# 506_outin_raspberrypi_zero.net
KiCad netlist of a schematic drawn in EAGLE
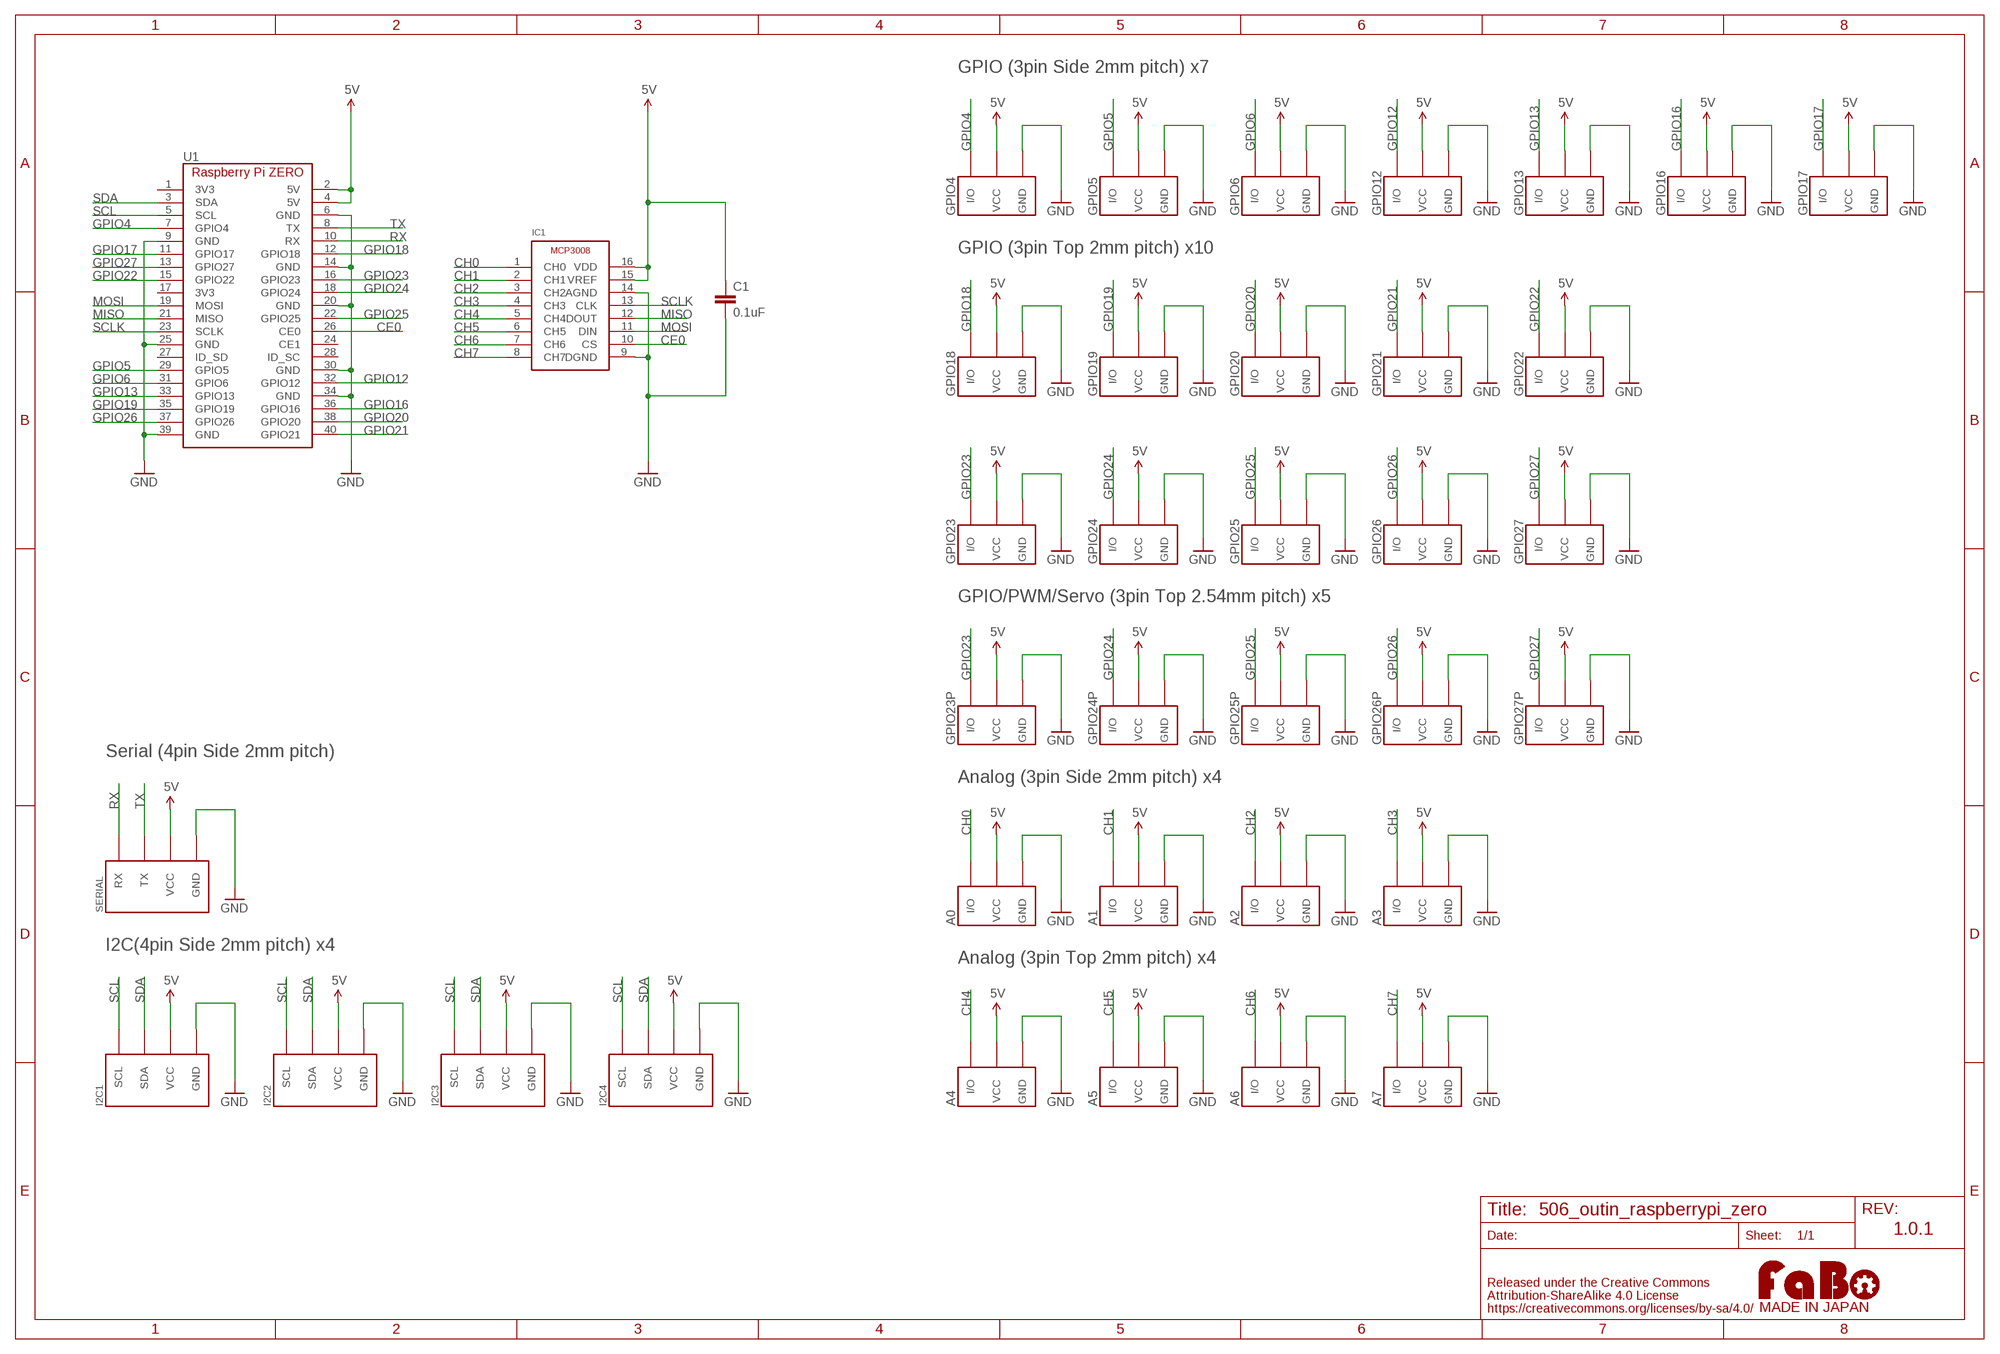
[diagram p0: schematic, sheet 1]

(export (version "E")
  (design (tool "Eeschema 10.0.6"))
  (components
    (comp (ref "A0")
      (value "FABO_BRICK_3PIN-S03B-PASK-2")
      (footprint "eagle-import:FABO_BRICK_3PIN_S03B-PASK-2")
      (libsource (lib "eagle-import") (part "FABO_BRICK_3PIN-S03B-PASK-2"))
    )
    (comp (ref "A1")
      (value "FABO_BRICK_3PIN-S03B-PASK-2")
      (footprint "eagle-import:FABO_BRICK_3PIN_S03B-PASK-2")
      (libsource (lib "eagle-import") (part "FABO_BRICK_3PIN-S03B-PASK-2"))
    )
    (comp (ref "A2")
      (value "FABO_BRICK_3PIN-S03B-PASK-2")
      (footprint "eagle-import:FABO_BRICK_3PIN_S03B-PASK-2")
      (libsource (lib "eagle-import") (part "FABO_BRICK_3PIN-S03B-PASK-2"))
    )
    (comp (ref "A3")
      (value "FABO_BRICK_3PIN-S03B-PASK-2")
      (footprint "eagle-import:FABO_BRICK_3PIN_S03B-PASK-2")
      (libsource (lib "eagle-import") (part "FABO_BRICK_3PIN-S03B-PASK-2"))
    )
    (comp (ref "A4")
      (value "FABO_BRICK_3PIN-B03B-PASK-1")
      (footprint "eagle-import:FABO_BRICK_3PIN_B03B-PASK-1")
      (libsource (lib "eagle-import") (part "FABO_BRICK_3PIN-B03B-PASK-1"))
    )
    (comp (ref "A5")
      (value "FABO_BRICK_3PIN-B03B-PASK-1")
      (footprint "eagle-import:FABO_BRICK_3PIN_B03B-PASK-1")
      (libsource (lib "eagle-import") (part "FABO_BRICK_3PIN-B03B-PASK-1"))
    )
    (comp (ref "A6")
      (value "FABO_BRICK_3PIN-B03B-PASK-1")
      (footprint "eagle-import:FABO_BRICK_3PIN_B03B-PASK-1")
      (libsource (lib "eagle-import") (part "FABO_BRICK_3PIN-B03B-PASK-1"))
    )
    (comp (ref "A7")
      (value "FABO_BRICK_3PIN-B03B-PASK-1")
      (footprint "eagle-import:FABO_BRICK_3PIN_B03B-PASK-1")
      (libsource (lib "eagle-import") (part "FABO_BRICK_3PIN-B03B-PASK-1"))
    )
    (comp (ref "C1")
      (value "0.1uF")
      (footprint "eagle-import:EIA0603")
      (libsource (lib "eagle-import") (part "CAP-EIA0603"))
    )
    (comp (ref "GPIO4")
      (value "FABO_BRICK_3PIN-S03B-PASK-2")
      (footprint "eagle-import:FABO_BRICK_3PIN_S03B-PASK-2")
      (libsource (lib "eagle-import") (part "FABO_BRICK_3PIN-S03B-PASK-2"))
    )
    (comp (ref "GPIO5")
      (value "FABO_BRICK_3PIN-S03B-PASK-2")
      (footprint "eagle-import:FABO_BRICK_3PIN_S03B-PASK-2")
      (libsource (lib "eagle-import") (part "FABO_BRICK_3PIN-S03B-PASK-2"))
    )
    (comp (ref "GPIO6")
      (value "FABO_BRICK_3PIN-S03B-PASK-2")
      (footprint "eagle-import:FABO_BRICK_3PIN_S03B-PASK-2")
      (libsource (lib "eagle-import") (part "FABO_BRICK_3PIN-S03B-PASK-2"))
    )
    (comp (ref "GPIO12")
      (value "FABO_BRICK_3PIN-S03B-PASK-2")
      (footprint "eagle-import:FABO_BRICK_3PIN_S03B-PASK-2")
      (libsource (lib "eagle-import") (part "FABO_BRICK_3PIN-S03B-PASK-2"))
    )
    (comp (ref "GPIO13")
      (value "FABO_BRICK_3PIN-S03B-PASK-2")
      (footprint "eagle-import:FABO_BRICK_3PIN_S03B-PASK-2")
      (libsource (lib "eagle-import") (part "FABO_BRICK_3PIN-S03B-PASK-2"))
    )
    (comp (ref "GPIO16")
      (value "FABO_BRICK_3PIN-S03B-PASK-2")
      (footprint "eagle-import:FABO_BRICK_3PIN_S03B-PASK-2")
      (libsource (lib "eagle-import") (part "FABO_BRICK_3PIN-S03B-PASK-2"))
    )
    (comp (ref "GPIO17")
      (value "FABO_BRICK_3PIN-S03B-PASK-2")
      (footprint "eagle-import:FABO_BRICK_3PIN_S03B-PASK-2")
      (libsource (lib "eagle-import") (part "FABO_BRICK_3PIN-S03B-PASK-2"))
    )
    (comp (ref "GPIO18")
      (value "FABO_BRICK_3PIN-B03B-PASK-1")
      (footprint "eagle-import:FABO_BRICK_3PIN_B03B-PASK-1")
      (libsource (lib "eagle-import") (part "FABO_BRICK_3PIN-B03B-PASK-1"))
    )
    (comp (ref "GPIO19")
      (value "FABO_BRICK_3PIN-B03B-PASK-1")
      (footprint "eagle-import:FABO_BRICK_3PIN_B03B-PASK-1")
      (libsource (lib "eagle-import") (part "FABO_BRICK_3PIN-B03B-PASK-1"))
    )
    (comp (ref "GPIO20")
      (value "FABO_BRICK_3PIN-B03B-PASK-1")
      (footprint "eagle-import:FABO_BRICK_3PIN_B03B-PASK-1")
      (libsource (lib "eagle-import") (part "FABO_BRICK_3PIN-B03B-PASK-1"))
    )
    (comp (ref "GPIO21")
      (value "FABO_BRICK_3PIN-B03B-PASK-1")
      (footprint "eagle-import:FABO_BRICK_3PIN_B03B-PASK-1")
      (libsource (lib "eagle-import") (part "FABO_BRICK_3PIN-B03B-PASK-1"))
    )
    (comp (ref "GPIO22")
      (value "FABO_BRICK_3PIN-B03B-PASK-1")
      (footprint "eagle-import:FABO_BRICK_3PIN_B03B-PASK-1")
      (libsource (lib "eagle-import") (part "FABO_BRICK_3PIN-B03B-PASK-1"))
    )
    (comp (ref "GPIO23")
      (value "FABO_BRICK_3PIN-B03B-PASK-1")
      (footprint "eagle-import:FABO_BRICK_3PIN_B03B-PASK-1")
      (libsource (lib "eagle-import") (part "FABO_BRICK_3PIN-B03B-PASK-1"))
    )
    (comp (ref "GPIO23P")
      (value "FABO_BRICK_3PIN-HEADER")
      (footprint "eagle-import:FABO_BRICK_3PIN_HEADER")
      (libsource (lib "eagle-import") (part "FABO_BRICK_3PIN-HEADER"))
    )
    (comp (ref "GPIO24")
      (value "FABO_BRICK_3PIN-B03B-PASK-1")
      (footprint "eagle-import:FABO_BRICK_3PIN_B03B-PASK-1")
      (libsource (lib "eagle-import") (part "FABO_BRICK_3PIN-B03B-PASK-1"))
    )
    (comp (ref "GPIO24P")
      (value "FABO_BRICK_3PIN-HEADER")
      (footprint "eagle-import:FABO_BRICK_3PIN_HEADER")
      (libsource (lib "eagle-import") (part "FABO_BRICK_3PIN-HEADER"))
    )
    (comp (ref "GPIO25")
      (value "FABO_BRICK_3PIN-B03B-PASK-1")
      (footprint "eagle-import:FABO_BRICK_3PIN_B03B-PASK-1")
      (libsource (lib "eagle-import") (part "FABO_BRICK_3PIN-B03B-PASK-1"))
    )
    (comp (ref "GPIO25P")
      (value "FABO_BRICK_3PIN-HEADER")
      (footprint "eagle-import:FABO_BRICK_3PIN_HEADER")
      (libsource (lib "eagle-import") (part "FABO_BRICK_3PIN-HEADER"))
    )
    (comp (ref "GPIO26")
      (value "FABO_BRICK_3PIN-B03B-PASK-1")
      (footprint "eagle-import:FABO_BRICK_3PIN_B03B-PASK-1")
      (libsource (lib "eagle-import") (part "FABO_BRICK_3PIN-B03B-PASK-1"))
    )
    (comp (ref "GPIO26P")
      (value "FABO_BRICK_3PIN-HEADER")
      (footprint "eagle-import:FABO_BRICK_3PIN_HEADER")
      (libsource (lib "eagle-import") (part "FABO_BRICK_3PIN-HEADER"))
    )
    (comp (ref "GPIO27")
      (value "FABO_BRICK_3PIN-B03B-PASK-1")
      (footprint "eagle-import:FABO_BRICK_3PIN_B03B-PASK-1")
      (libsource (lib "eagle-import") (part "FABO_BRICK_3PIN-B03B-PASK-1"))
    )
    (comp (ref "GPIO27P")
      (value "FABO_BRICK_3PIN-HEADER")
      (footprint "eagle-import:FABO_BRICK_3PIN_HEADER")
      (libsource (lib "eagle-import") (part "FABO_BRICK_3PIN-HEADER"))
    )
    (comp (ref "I2C1")
      (value "FABO_BRICK_I2C-S04B-PASK-2")
      (footprint "eagle-import:FABO_BRICK_I2C_S04B-PASK-2")
      (libsource (lib "eagle-import") (part "FABO_BRICK_I2C-S04B-PASK-2"))
    )
    (comp (ref "I2C2")
      (value "FABO_BRICK_I2C-S04B-PASK-2")
      (footprint "eagle-import:FABO_BRICK_I2C_S04B-PASK-2")
      (libsource (lib "eagle-import") (part "FABO_BRICK_I2C-S04B-PASK-2"))
    )
    (comp (ref "I2C3")
      (value "FABO_BRICK_I2C-S04B-PASK-2")
      (footprint "eagle-import:FABO_BRICK_I2C_S04B-PASK-2")
      (libsource (lib "eagle-import") (part "FABO_BRICK_I2C-S04B-PASK-2"))
    )
    (comp (ref "I2C4")
      (value "FABO_BRICK_I2C-S04B-PASK-2")
      (footprint "eagle-import:FABO_BRICK_I2C_S04B-PASK-2")
      (libsource (lib "eagle-import") (part "FABO_BRICK_I2C-S04B-PASK-2"))
    )
    (comp (ref "IC1")
      (value "MICROCHIP-MCP3008")
      (footprint "eagle-import:MICROCHIP-MCP3008")
      (libsource (lib "eagle-import") (part "MICROCHIP-MCP3008"))
    )
    (comp (ref "SERIAL")
      (value "FABO_BRICK_SERIAL-S04B-PASK-2")
      (footprint "eagle-import:FABO_BRICK_SERIAL_S04B-PASK-2")
      (libsource (lib "eagle-import") (part "FABO_BRICK_SERIAL-S04B-PASK-2"))
    )
    (comp (ref "U$14")
      (value "LOGO_FABO-M")
      (footprint "eagle-import:LOGO_FABO_MS")
      (libsource (lib "eagle-import") (part "LOGO_FABO-M"))
    )
    (comp (ref "U1")
      (value "RASPBERRY_PI_ZERO")
      (footprint "eagle-import:RASPBERRY_PI_ZERO")
      (libsource (lib "eagle-import") (part "RASPBERRY_PI_ZERO"))
    )
  )
  (nets
    (net (code "1") (name "/CE0") (class "Default")
      (node (ref "IC1") (pin "10") (pinfunction "CS_10") (pintype "bidirectional"))
      (node (ref "U1") (pin "26") (pinfunction "CE0_26") (pintype "bidirectional"))
    )
    (net (code "2") (name "/CH0") (class "Default")
      (node (ref "A0") (pin "I/O") (pinfunction "I/O_I/O") (pintype "bidirectional"))
      (node (ref "IC1") (pin "1") (pinfunction "CH0_1") (pintype "bidirectional"))
    )
    (net (code "3") (name "/CH1") (class "Default")
      (node (ref "A1") (pin "I/O") (pinfunction "I/O_I/O") (pintype "bidirectional"))
      (node (ref "IC1") (pin "2") (pinfunction "CH1_2") (pintype "bidirectional"))
    )
    (net (code "4") (name "/CH2") (class "Default")
      (node (ref "A2") (pin "I/O") (pinfunction "I/O_I/O") (pintype "bidirectional"))
      (node (ref "IC1") (pin "3") (pinfunction "CH2_3") (pintype "bidirectional"))
    )
    (net (code "5") (name "/CH3") (class "Default")
      (node (ref "A3") (pin "I/O") (pinfunction "I/O_I/O") (pintype "bidirectional"))
      (node (ref "IC1") (pin "4") (pinfunction "CH3_4") (pintype "bidirectional"))
    )
    (net (code "6") (name "/CH4") (class "Default")
      (node (ref "A4") (pin "I/O") (pinfunction "I/O_I/O") (pintype "bidirectional"))
      (node (ref "IC1") (pin "5") (pinfunction "CH4_5") (pintype "bidirectional"))
    )
    (net (code "7") (name "/CH5") (class "Default")
      (node (ref "A5") (pin "I/O") (pinfunction "I/O_I/O") (pintype "bidirectional"))
      (node (ref "IC1") (pin "6") (pinfunction "CH5_6") (pintype "bidirectional"))
    )
    (net (code "8") (name "/CH6") (class "Default")
      (node (ref "A6") (pin "I/O") (pinfunction "I/O_I/O") (pintype "bidirectional"))
      (node (ref "IC1") (pin "7") (pinfunction "CH6_7") (pintype "bidirectional"))
    )
    (net (code "9") (name "/CH7") (class "Default")
      (node (ref "A7") (pin "I/O") (pinfunction "I/O_I/O") (pintype "bidirectional"))
      (node (ref "IC1") (pin "8") (pinfunction "CH7_8") (pintype "bidirectional"))
    )
    (net (code "10") (name "/GPIO4") (class "Default")
      (node (ref "GPIO4") (pin "I/O") (pinfunction "I/O_I/O") (pintype "bidirectional"))
      (node (ref "U1") (pin "7") (pinfunction "GPIO4_7") (pintype "bidirectional"))
    )
    (net (code "11") (name "/GPIO5") (class "Default")
      (node (ref "GPIO5") (pin "I/O") (pinfunction "I/O_I/O") (pintype "bidirectional"))
      (node (ref "U1") (pin "29") (pinfunction "GPIO5_29") (pintype "bidirectional"))
    )
    (net (code "12") (name "/GPIO6") (class "Default")
      (node (ref "GPIO6") (pin "I/O") (pinfunction "I/O_I/O") (pintype "bidirectional"))
      (node (ref "U1") (pin "31") (pinfunction "GPIO6_31") (pintype "bidirectional"))
    )
    (net (code "13") (name "/GPIO12") (class "Default")
      (node (ref "GPIO12") (pin "I/O") (pinfunction "I/O_I/O") (pintype "bidirectional"))
      (node (ref "U1") (pin "32") (pinfunction "GPIO12_32") (pintype "bidirectional"))
    )
    (net (code "14") (name "/GPIO13") (class "Default")
      (node (ref "GPIO13") (pin "I/O") (pinfunction "I/O_I/O") (pintype "bidirectional"))
      (node (ref "U1") (pin "33") (pinfunction "GPIO13_33") (pintype "bidirectional"))
    )
    (net (code "15") (name "/GPIO16") (class "Default")
      (node (ref "GPIO16") (pin "I/O") (pinfunction "I/O_I/O") (pintype "bidirectional"))
      (node (ref "U1") (pin "36") (pinfunction "GPIO16_36") (pintype "bidirectional"))
    )
    (net (code "16") (name "/GPIO17") (class "Default")
      (node (ref "GPIO17") (pin "I/O") (pinfunction "I/O_I/O") (pintype "bidirectional"))
      (node (ref "U1") (pin "11") (pinfunction "GPIO17_11") (pintype "bidirectional"))
    )
    (net (code "17") (name "/GPIO18") (class "Default")
      (node (ref "GPIO18") (pin "I/O") (pinfunction "I/O_I/O") (pintype "bidirectional"))
      (node (ref "U1") (pin "12") (pinfunction "GPIO18_12") (pintype "bidirectional"))
    )
    (net (code "18") (name "/GPIO19") (class "Default")
      (node (ref "GPIO19") (pin "I/O") (pinfunction "I/O_I/O") (pintype "bidirectional"))
      (node (ref "U1") (pin "35") (pinfunction "GPIO19_35") (pintype "bidirectional"))
    )
    (net (code "19") (name "/GPIO20") (class "Default")
      (node (ref "GPIO20") (pin "I/O") (pinfunction "I/O_I/O") (pintype "bidirectional"))
      (node (ref "U1") (pin "38") (pinfunction "GPIO20_38") (pintype "bidirectional"))
    )
    (net (code "20") (name "/GPIO21") (class "Default")
      (node (ref "GPIO21") (pin "I/O") (pinfunction "I/O_I/O") (pintype "bidirectional"))
      (node (ref "U1") (pin "40") (pinfunction "GPIO21_40") (pintype "bidirectional"))
    )
    (net (code "21") (name "/GPIO22") (class "Default")
      (node (ref "GPIO22") (pin "I/O") (pinfunction "I/O_I/O") (pintype "bidirectional"))
      (node (ref "U1") (pin "15") (pinfunction "GPIO22_15") (pintype "bidirectional"))
    )
    (net (code "22") (name "/GPIO23") (class "Default")
      (node (ref "GPIO23") (pin "I/O") (pinfunction "I/O_I/O") (pintype "bidirectional"))
      (node (ref "GPIO23P") (pin "I/O") (pinfunction "I/O_I/O") (pintype "bidirectional"))
      (node (ref "U1") (pin "16") (pinfunction "GPIO23_16") (pintype "bidirectional"))
    )
    (net (code "23") (name "/GPIO24") (class "Default")
      (node (ref "GPIO24") (pin "I/O") (pinfunction "I/O_I/O") (pintype "bidirectional"))
      (node (ref "GPIO24P") (pin "I/O") (pinfunction "I/O_I/O") (pintype "bidirectional"))
      (node (ref "U1") (pin "18") (pinfunction "GPIO24_18") (pintype "bidirectional"))
    )
    (net (code "24") (name "/GPIO25") (class "Default")
      (node (ref "GPIO25") (pin "I/O") (pinfunction "I/O_I/O") (pintype "bidirectional"))
      (node (ref "GPIO25P") (pin "I/O") (pinfunction "I/O_I/O") (pintype "bidirectional"))
      (node (ref "U1") (pin "22") (pinfunction "GPIO25_22") (pintype "bidirectional"))
    )
    (net (code "25") (name "/GPIO26") (class "Default")
      (node (ref "GPIO26") (pin "I/O") (pinfunction "I/O_I/O") (pintype "bidirectional"))
      (node (ref "GPIO26P") (pin "I/O") (pinfunction "I/O_I/O") (pintype "bidirectional"))
      (node (ref "U1") (pin "37") (pinfunction "GPIO26_37") (pintype "bidirectional"))
    )
    (net (code "26") (name "/GPIO27") (class "Default")
      (node (ref "GPIO27") (pin "I/O") (pinfunction "I/O_I/O") (pintype "bidirectional"))
      (node (ref "GPIO27P") (pin "I/O") (pinfunction "I/O_I/O") (pintype "bidirectional"))
      (node (ref "U1") (pin "13") (pinfunction "GPIO27_13") (pintype "bidirectional"))
    )
    (net (code "27") (name "/MISO") (class "Default")
      (node (ref "IC1") (pin "12") (pinfunction "DOUT_12") (pintype "bidirectional"))
      (node (ref "U1") (pin "21") (pinfunction "MISO_21") (pintype "bidirectional"))
    )
    (net (code "28") (name "/MOSI") (class "Default")
      (node (ref "IC1") (pin "11") (pinfunction "DIN_11") (pintype "bidirectional"))
      (node (ref "U1") (pin "19") (pinfunction "MOSI_19") (pintype "bidirectional"))
    )
    (net (code "29") (name "/RX") (class "Default")
      (node (ref "SERIAL") (pin "RX") (pinfunction "RX_RX") (pintype "bidirectional"))
      (node (ref "U1") (pin "10") (pinfunction "RX_10") (pintype "bidirectional"))
    )
    (net (code "30") (name "/SCL") (class "Default")
      (node (ref "I2C1") (pin "SCL") (pinfunction "SCL_SCL") (pintype "bidirectional"))
      (node (ref "I2C2") (pin "SCL") (pinfunction "SCL_SCL") (pintype "bidirectional"))
      (node (ref "I2C3") (pin "SCL") (pinfunction "SCL_SCL") (pintype "bidirectional"))
      (node (ref "I2C4") (pin "SCL") (pinfunction "SCL_SCL") (pintype "bidirectional"))
      (node (ref "U1") (pin "5") (pinfunction "SCL_5") (pintype "bidirectional"))
    )
    (net (code "31") (name "/SCLK") (class "Default")
      (node (ref "IC1") (pin "13") (pinfunction "CLK_13") (pintype "bidirectional"))
      (node (ref "U1") (pin "23") (pinfunction "SCLK_23") (pintype "bidirectional"))
    )
    (net (code "32") (name "/SDA") (class "Default")
      (node (ref "I2C1") (pin "SDA") (pinfunction "SDA_SDA") (pintype "bidirectional"))
      (node (ref "I2C2") (pin "SDA") (pinfunction "SDA_SDA") (pintype "bidirectional"))
      (node (ref "I2C3") (pin "SDA") (pinfunction "SDA_SDA") (pintype "bidirectional"))
      (node (ref "I2C4") (pin "SDA") (pinfunction "SDA_SDA") (pintype "bidirectional"))
      (node (ref "U1") (pin "3") (pinfunction "SDA_3") (pintype "bidirectional"))
    )
    (net (code "33") (name "/TX") (class "Default")
      (node (ref "SERIAL") (pin "TX") (pinfunction "TX_TX") (pintype "bidirectional"))
      (node (ref "U1") (pin "8") (pinfunction "TX_8") (pintype "bidirectional"))
    )
    (net (code "34") (name "5V") (class "Default")
      (node (ref "A0") (pin "VCC") (pinfunction "VCC_VCC") (pintype "bidirectional"))
      (node (ref "A1") (pin "VCC") (pinfunction "VCC_VCC") (pintype "bidirectional"))
      (node (ref "A2") (pin "VCC") (pinfunction "VCC_VCC") (pintype "bidirectional"))
      (node (ref "A3") (pin "VCC") (pinfunction "VCC_VCC") (pintype "bidirectional"))
      (node (ref "A4") (pin "VCC") (pinfunction "VCC_VCC") (pintype "bidirectional"))
      (node (ref "A5") (pin "VCC") (pinfunction "VCC_VCC") (pintype "bidirectional"))
      (node (ref "A6") (pin "VCC") (pinfunction "VCC_VCC") (pintype "bidirectional"))
      (node (ref "A7") (pin "VCC") (pinfunction "VCC_VCC") (pintype "bidirectional"))
      (node (ref "C1") (pin "1") (pinfunction "1_1") (pintype "passive"))
      (node (ref "GPIO12") (pin "VCC") (pinfunction "VCC_VCC") (pintype "bidirectional"))
      (node (ref "GPIO13") (pin "VCC") (pinfunction "VCC_VCC") (pintype "bidirectional"))
      (node (ref "GPIO16") (pin "VCC") (pinfunction "VCC_VCC") (pintype "bidirectional"))
      (node (ref "GPIO17") (pin "VCC") (pinfunction "VCC_VCC") (pintype "bidirectional"))
      (node (ref "GPIO18") (pin "VCC") (pinfunction "VCC_VCC") (pintype "bidirectional"))
      (node (ref "GPIO19") (pin "VCC") (pinfunction "VCC_VCC") (pintype "bidirectional"))
      (node (ref "GPIO20") (pin "VCC") (pinfunction "VCC_VCC") (pintype "bidirectional"))
      (node (ref "GPIO21") (pin "VCC") (pinfunction "VCC_VCC") (pintype "bidirectional"))
      (node (ref "GPIO22") (pin "VCC") (pinfunction "VCC_VCC") (pintype "bidirectional"))
      (node (ref "GPIO23") (pin "VCC") (pinfunction "VCC_VCC") (pintype "bidirectional"))
      (node (ref "GPIO23P") (pin "VCC") (pinfunction "VCC_VCC") (pintype "bidirectional"))
      (node (ref "GPIO24") (pin "VCC") (pinfunction "VCC_VCC") (pintype "bidirectional"))
      (node (ref "GPIO24P") (pin "VCC") (pinfunction "VCC_VCC") (pintype "bidirectional"))
      (node (ref "GPIO25") (pin "VCC") (pinfunction "VCC_VCC") (pintype "bidirectional"))
      (node (ref "GPIO25P") (pin "VCC") (pinfunction "VCC_VCC") (pintype "bidirectional"))
      (node (ref "GPIO26") (pin "VCC") (pinfunction "VCC_VCC") (pintype "bidirectional"))
      (node (ref "GPIO26P") (pin "VCC") (pinfunction "VCC_VCC") (pintype "bidirectional"))
      (node (ref "GPIO27") (pin "VCC") (pinfunction "VCC_VCC") (pintype "bidirectional"))
      (node (ref "GPIO27P") (pin "VCC") (pinfunction "VCC_VCC") (pintype "bidirectional"))
      (node (ref "GPIO4") (pin "VCC") (pinfunction "VCC_VCC") (pintype "bidirectional"))
      (node (ref "GPIO5") (pin "VCC") (pinfunction "VCC_VCC") (pintype "bidirectional"))
      (node (ref "GPIO6") (pin "VCC") (pinfunction "VCC_VCC") (pintype "bidirectional"))
      (node (ref "I2C1") (pin "VCC") (pinfunction "VCC_VCC") (pintype "bidirectional"))
      (node (ref "I2C2") (pin "VCC") (pinfunction "VCC_VCC") (pintype "bidirectional"))
      (node (ref "I2C3") (pin "VCC") (pinfunction "VCC_VCC") (pintype "bidirectional"))
      (node (ref "I2C4") (pin "VCC") (pinfunction "VCC_VCC") (pintype "bidirectional"))
      (node (ref "IC1") (pin "15") (pinfunction "VREF_15") (pintype "bidirectional"))
      (node (ref "IC1") (pin "16") (pinfunction "VDD_16") (pintype "bidirectional"))
      (node (ref "SERIAL") (pin "VCC") (pinfunction "VCC_VCC") (pintype "bidirectional"))
      (node (ref "U1") (pin "2") (pinfunction "5V_2") (pintype "bidirectional"))
      (node (ref "U1") (pin "4") (pinfunction "5V_4") (pintype "bidirectional"))
    )
    (net (code "35") (name "GND") (class "Default")
      (node (ref "A0") (pin "GND") (pinfunction "GND_GND") (pintype "bidirectional"))
      (node (ref "A1") (pin "GND") (pinfunction "GND_GND") (pintype "bidirectional"))
      (node (ref "A2") (pin "GND") (pinfunction "GND_GND") (pintype "bidirectional"))
      (node (ref "A3") (pin "GND") (pinfunction "GND_GND") (pintype "bidirectional"))
      (node (ref "A4") (pin "GND") (pinfunction "GND_GND") (pintype "bidirectional"))
      (node (ref "A5") (pin "GND") (pinfunction "GND_GND") (pintype "bidirectional"))
      (node (ref "A6") (pin "GND") (pinfunction "GND_GND") (pintype "bidirectional"))
      (node (ref "A7") (pin "GND") (pinfunction "GND_GND") (pintype "bidirectional"))
      (node (ref "C1") (pin "2") (pinfunction "2_2") (pintype "passive"))
      (node (ref "GPIO12") (pin "GND") (pinfunction "GND_GND") (pintype "bidirectional"))
      (node (ref "GPIO13") (pin "GND") (pinfunction "GND_GND") (pintype "bidirectional"))
      (node (ref "GPIO16") (pin "GND") (pinfunction "GND_GND") (pintype "bidirectional"))
      (node (ref "GPIO17") (pin "GND") (pinfunction "GND_GND") (pintype "bidirectional"))
      (node (ref "GPIO18") (pin "GND") (pinfunction "GND_GND") (pintype "bidirectional"))
      (node (ref "GPIO19") (pin "GND") (pinfunction "GND_GND") (pintype "bidirectional"))
      (node (ref "GPIO20") (pin "GND") (pinfunction "GND_GND") (pintype "bidirectional"))
      (node (ref "GPIO21") (pin "GND") (pinfunction "GND_GND") (pintype "bidirectional"))
      (node (ref "GPIO22") (pin "GND") (pinfunction "GND_GND") (pintype "bidirectional"))
      (node (ref "GPIO23") (pin "GND") (pinfunction "GND_GND") (pintype "bidirectional"))
      (node (ref "GPIO23P") (pin "GND") (pinfunction "GND_GND") (pintype "bidirectional"))
      (node (ref "GPIO24") (pin "GND") (pinfunction "GND_GND") (pintype "bidirectional"))
      (node (ref "GPIO24P") (pin "GND") (pinfunction "GND_GND") (pintype "bidirectional"))
      (node (ref "GPIO25") (pin "GND") (pinfunction "GND_GND") (pintype "bidirectional"))
      (node (ref "GPIO25P") (pin "GND") (pinfunction "GND_GND") (pintype "bidirectional"))
      (node (ref "GPIO26") (pin "GND") (pinfunction "GND_GND") (pintype "bidirectional"))
      (node (ref "GPIO26P") (pin "GND") (pinfunction "GND_GND") (pintype "bidirectional"))
      (node (ref "GPIO27") (pin "GND") (pinfunction "GND_GND") (pintype "bidirectional"))
      (node (ref "GPIO27P") (pin "GND") (pinfunction "GND_GND") (pintype "bidirectional"))
      (node (ref "GPIO4") (pin "GND") (pinfunction "GND_GND") (pintype "bidirectional"))
      (node (ref "GPIO5") (pin "GND") (pinfunction "GND_GND") (pintype "bidirectional"))
      (node (ref "GPIO6") (pin "GND") (pinfunction "GND_GND") (pintype "bidirectional"))
      (node (ref "I2C1") (pin "GND") (pinfunction "GND_GND") (pintype "bidirectional"))
      (node (ref "I2C2") (pin "GND") (pinfunction "GND_GND") (pintype "bidirectional"))
      (node (ref "I2C3") (pin "GND") (pinfunction "GND_GND") (pintype "bidirectional"))
      (node (ref "I2C4") (pin "GND") (pinfunction "GND_GND") (pintype "bidirectional"))
      (node (ref "IC1") (pin "14") (pinfunction "AGND_14") (pintype "bidirectional"))
      (node (ref "IC1") (pin "9") (pinfunction "DGND_9") (pintype "bidirectional"))
      (node (ref "SERIAL") (pin "GND") (pinfunction "GND_GND") (pintype "bidirectional"))
      (node (ref "U1") (pin "14") (pinfunction "GND_14") (pintype "bidirectional"))
      (node (ref "U1") (pin "20") (pinfunction "GND_20") (pintype "bidirectional"))
      (node (ref "U1") (pin "25") (pinfunction "GND_25") (pintype "bidirectional"))
      (node (ref "U1") (pin "30") (pinfunction "GND_30") (pintype "bidirectional"))
      (node (ref "U1") (pin "34") (pinfunction "GND_34") (pintype "bidirectional"))
      (node (ref "U1") (pin "39") (pinfunction "GND_39") (pintype "bidirectional"))
      (node (ref "U1") (pin "6") (pinfunction "GND_6") (pintype "bidirectional"))
      (node (ref "U1") (pin "9") (pinfunction "GND_9") (pintype "bidirectional"))
    )
    (net (code "36") (name "unconnected-(U1-3V3-Pad1)") (class "Default")
      (node (ref "U1") (pin "1") (pinfunction "3V3_1") (pintype "bidirectional"))
    )
    (net (code "37") (name "unconnected-(U1-3V3-Pad17)") (class "Default")
      (node (ref "U1") (pin "17") (pinfunction "3V3_17") (pintype "bidirectional"))
    )
    (net (code "38") (name "unconnected-(U1-CE1-Pad24)") (class "Default")
      (node (ref "U1") (pin "24") (pinfunction "CE1_24") (pintype "bidirectional"))
    )
    (net (code "39") (name "unconnected-(U1-ID_SC-Pad28)") (class "Default")
      (node (ref "U1") (pin "28") (pinfunction "ID_SC_28") (pintype "bidirectional"))
    )
    (net (code "40") (name "unconnected-(U1-ID_SD-Pad27)") (class "Default")
      (node (ref "U1") (pin "27") (pinfunction "ID_SD_27") (pintype "bidirectional"))
    )
  )
)
